# SchematicEasyEDA.net
KiCad netlist of a schematic drawn in EasyEDA
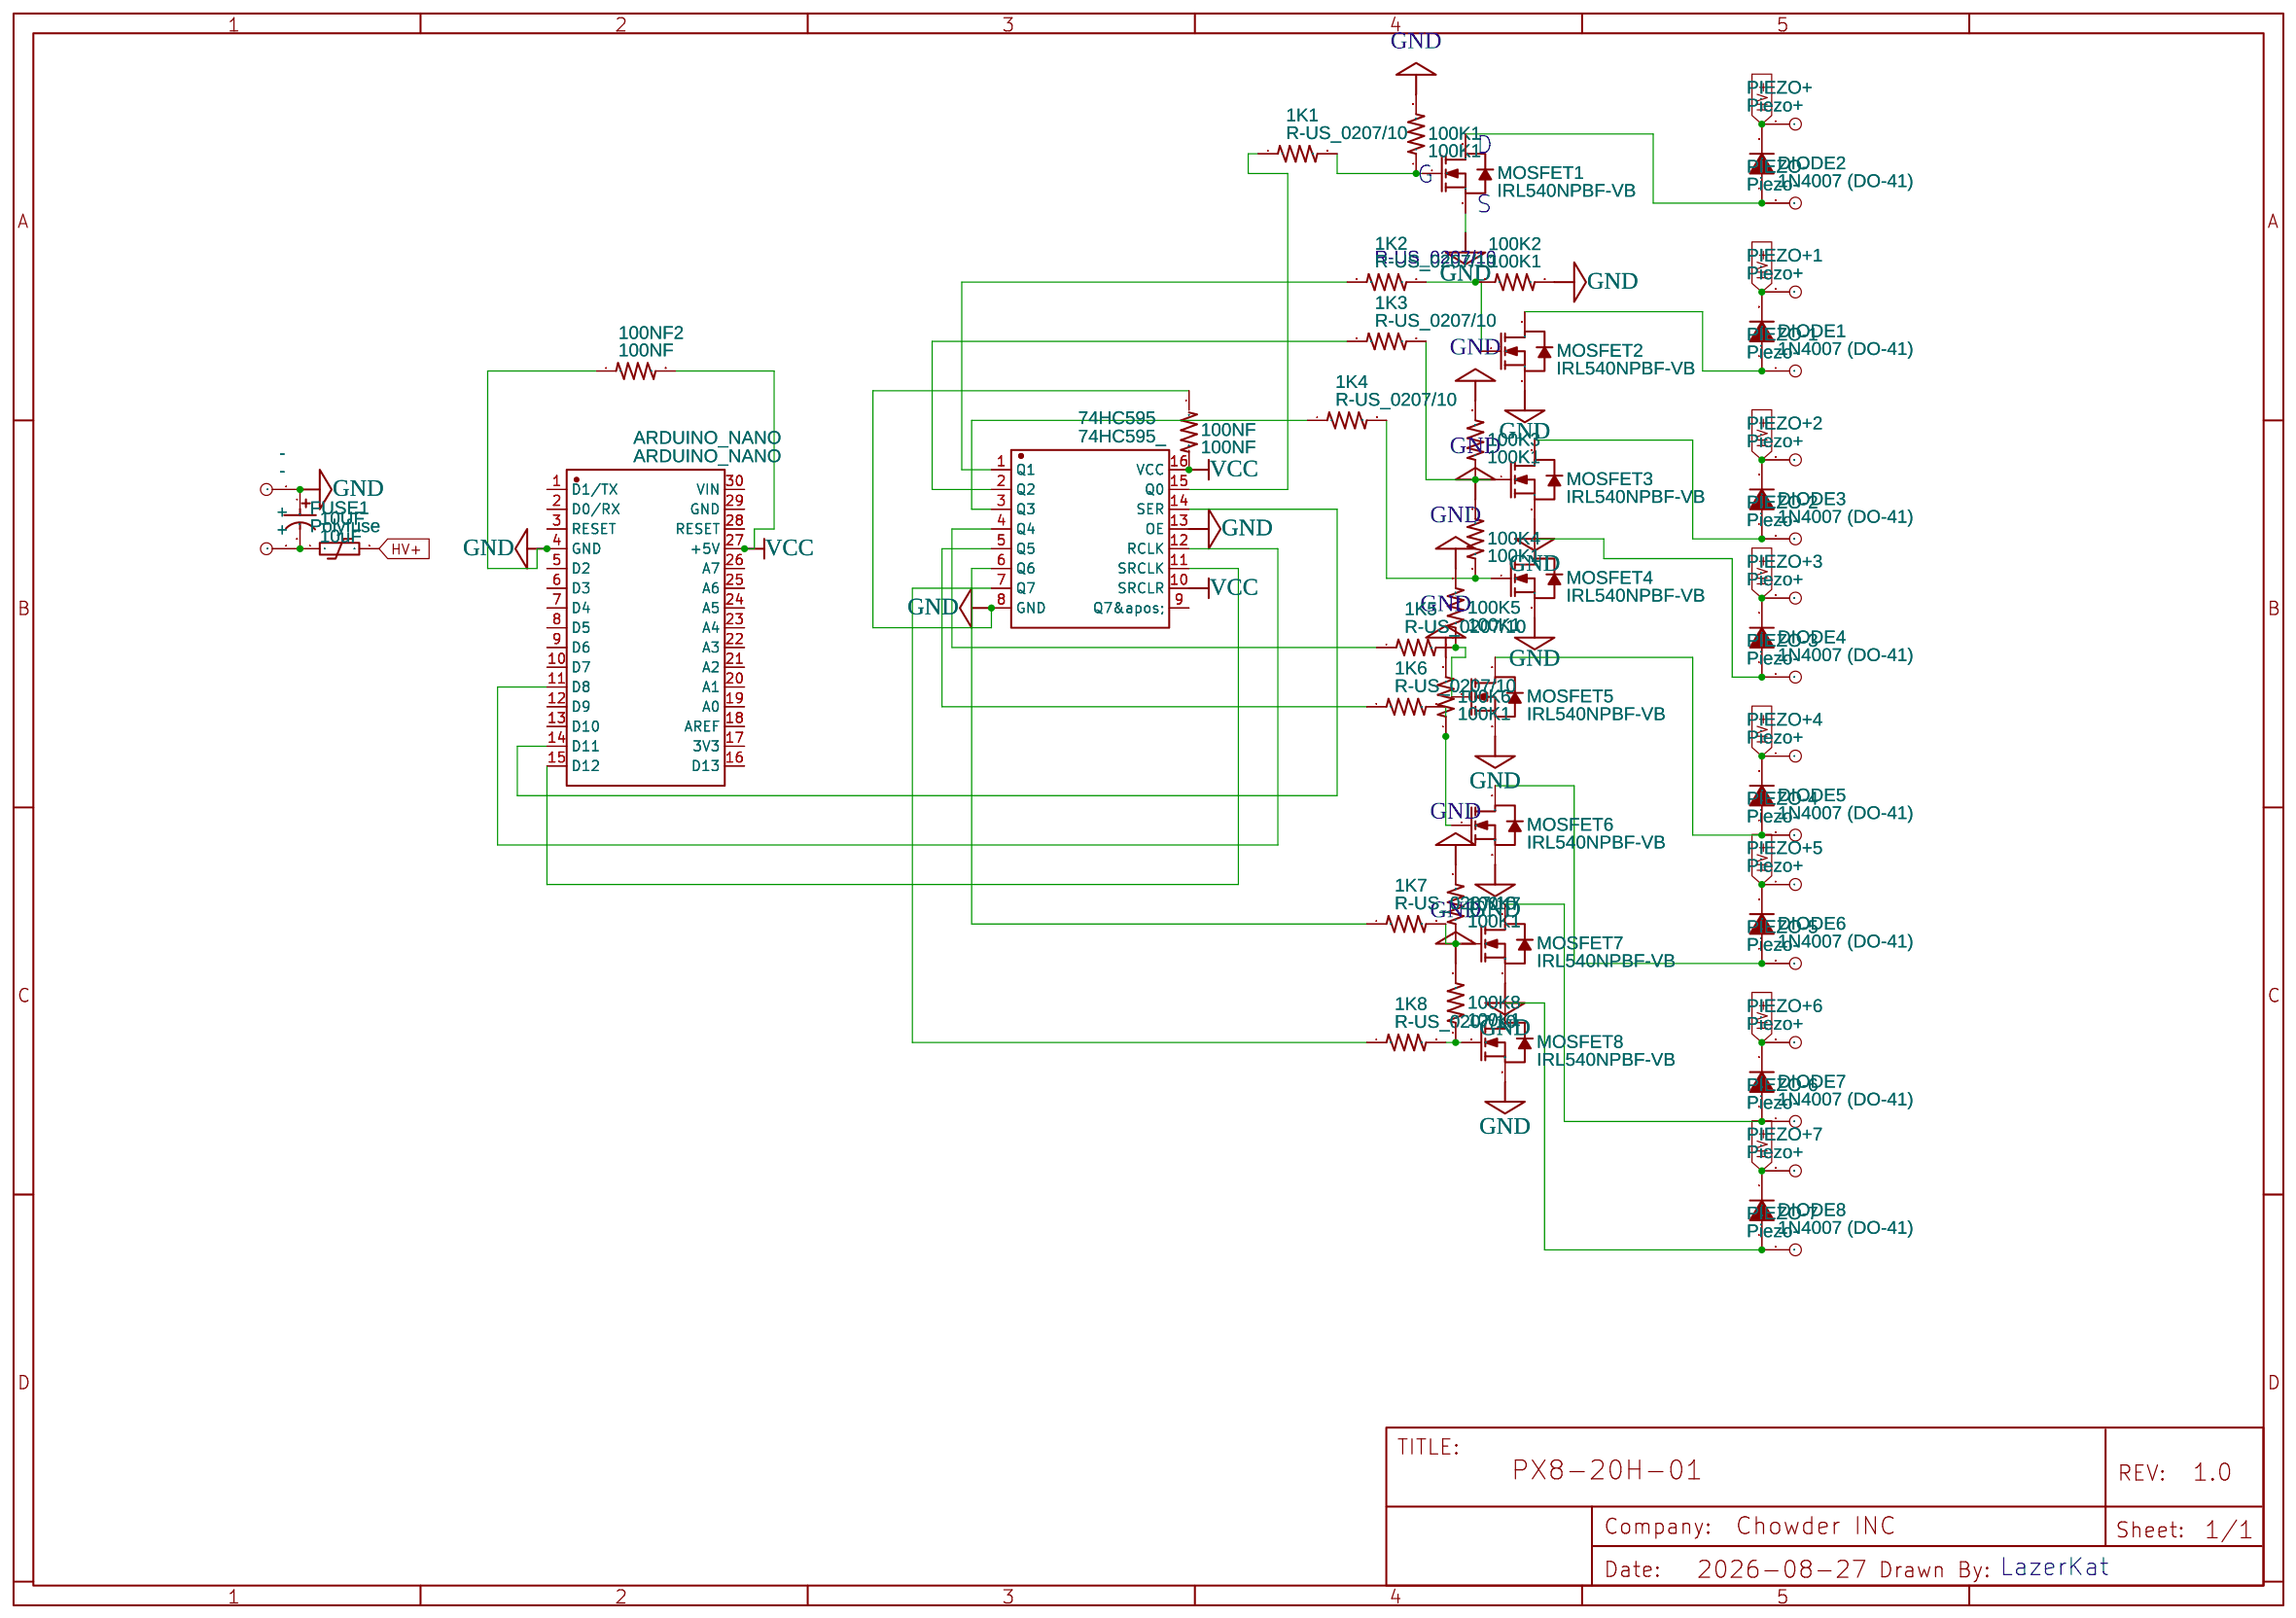
[diagram p0: schematic sheet]

(export (version "E")
  (design (tool "Eeschema 10.0.6"))
  (components
    (comp (ref "+") (value "+") (libsource (lib "") (part "Through-hole pin_3")))
    (comp (ref "-") (value "-") (libsource (lib "") (part "Through-hole pin_2")))
    (comp (ref "1K1") (value "R-US_0207/10") (libsource (lib "") (part "R-US_0207/10")))
    (comp (ref "1K2") (value "R-US_0207/10") (libsource (lib "") (part "R-US_0207/10")))
    (comp (ref "1K3") (value "R-US_0207/10") (libsource (lib "") (part "R-US_0207/10")))
    (comp (ref "1K4") (value "R-US_0207/10") (libsource (lib "") (part "R-US_0207/10")))
    (comp (ref "1K5") (value "R-US_0207/10") (libsource (lib "") (part "R-US_0207/10")))
    (comp (ref "1K6") (value "R-US_0207/10") (libsource (lib "") (part "R-US_0207/10")))
    (comp (ref "1K7") (value "R-US_0207/10") (libsource (lib "") (part "R-US_0207/10")))
    (comp (ref "1K8") (value "R-US_0207/10") (libsource (lib "") (part "R-US_0207/10")))
    (comp (ref "10UF")
      (value "10uF")
      (fields (field (name "Manufacturer Part") "ERS1KM100E11OT") (field (name "Manufacturer") "AISHI"))
      (libsource (lib "") (part "10UF 100V"))
    )
    (comp (ref "74HC595")
      (value "74HC595_")
      (fields (field (name "Manufacturer Part") "74HC595A") (field (name "Manufacturer") "FM"))
      (libsource (lib "") (part "74HC595_"))
    )
    (comp (ref "100K1") (value "100K1") (libsource (lib "") (part "R-US_0207/10_1")))
    (comp (ref "100K2") (value "100K1") (libsource (lib "") (part "R-US_0207/10_2")))
    (comp (ref "100K3") (value "100K1") (libsource (lib "") (part "R-US_0207/10_1")))
    (comp (ref "100K4") (value "100K1") (libsource (lib "") (part "R-US_0207/10_1")))
    (comp (ref "100K5") (value "100K1") (libsource (lib "") (part "R-US_0207/10_1")))
    (comp (ref "100K6") (value "100K1") (libsource (lib "") (part "R-US_0207/10_1")))
    (comp (ref "100K7") (value "100K1") (libsource (lib "") (part "R-US_0207/10_1")))
    (comp (ref "100K8") (value "100K1") (libsource (lib "") (part "R-US_0207/10_1")))
    (comp (ref "100NF") (value "100NF") (libsource (lib "") (part "R-US_0207/10_3")))
    (comp (ref "100NF2") (value "100NF") (libsource (lib "") (part "R-US_0207/10_4")))
    (comp (ref "ARDUINO_NANO") (value "ARDUINO_NANO") (libsource (lib "") (part "ARDUINO_NANO")))
    (comp (ref "DIODE1")
      (value "1N4007 (DO-41)")
      (fields (field (name "Manufacturer Part") "1 N 4007"))
      (libsource (lib "") (part "1N4007 (DO-41)"))
    )
    (comp (ref "DIODE2")
      (value "1N4007 (DO-41)")
      (fields (field (name "Manufacturer Part") "1 N 4007"))
      (libsource (lib "") (part "1N4007 (DO-41)"))
    )
    (comp (ref "DIODE3")
      (value "1N4007 (DO-41)")
      (fields (field (name "Manufacturer Part") "1 N 4007"))
      (libsource (lib "") (part "1N4007 (DO-41)"))
    )
    (comp (ref "DIODE4")
      (value "1N4007 (DO-41)")
      (fields (field (name "Manufacturer Part") "1 N 4007"))
      (libsource (lib "") (part "1N4007 (DO-41)"))
    )
    (comp (ref "DIODE5")
      (value "1N4007 (DO-41)")
      (fields (field (name "Manufacturer Part") "1 N 4007"))
      (libsource (lib "") (part "1N4007 (DO-41)"))
    )
    (comp (ref "DIODE6")
      (value "1N4007 (DO-41)")
      (fields (field (name "Manufacturer Part") "1 N 4007"))
      (libsource (lib "") (part "1N4007 (DO-41)"))
    )
    (comp (ref "DIODE7")
      (value "1N4007 (DO-41)")
      (fields (field (name "Manufacturer Part") "1 N 4007"))
      (libsource (lib "") (part "1N4007 (DO-41)"))
    )
    (comp (ref "DIODE8")
      (value "1N4007 (DO-41)")
      (fields (field (name "Manufacturer Part") "1 N 4007"))
      (libsource (lib "") (part "1N4007 (DO-41)"))
    )
    (comp (ref "FUSE1") (value "Polyfuse") (libsource (lib "") (part "Polyfuse")))
    (comp (ref "MOSFET1")
      (value "IRL540NPBF-VB")
      (fields (field (name "Manufacturer") "VBsemi(微碧半导体)"))
      (libsource (lib "") (part "IRL540NPBF-VB"))
    )
    (comp (ref "MOSFET2")
      (value "IRL540NPBF-VB")
      (fields (field (name "Manufacturer") "VBsemi(微碧半导体)"))
      (libsource (lib "") (part "IRL540NPBF-VB"))
    )
    (comp (ref "MOSFET3")
      (value "IRL540NPBF-VB")
      (fields (field (name "Manufacturer") "VBsemi(微碧半导体)"))
      (libsource (lib "") (part "IRL540NPBF-VB"))
    )
    (comp (ref "MOSFET4")
      (value "IRL540NPBF-VB")
      (fields (field (name "Manufacturer") "VBsemi(微碧半导体)"))
      (libsource (lib "") (part "IRL540NPBF-VB"))
    )
    (comp (ref "MOSFET5")
      (value "IRL540NPBF-VB")
      (fields (field (name "Manufacturer") "VBsemi(微碧半导体)"))
      (libsource (lib "") (part "IRL540NPBF-VB"))
    )
    (comp (ref "MOSFET6")
      (value "IRL540NPBF-VB")
      (fields (field (name "Manufacturer") "VBsemi(微碧半导体)"))
      (libsource (lib "") (part "IRL540NPBF-VB"))
    )
    (comp (ref "MOSFET7")
      (value "IRL540NPBF-VB")
      (fields (field (name "Manufacturer") "VBsemi(微碧半导体)"))
      (libsource (lib "") (part "IRL540NPBF-VB"))
    )
    (comp (ref "MOSFET8")
      (value "IRL540NPBF-VB")
      (fields (field (name "Manufacturer") "VBsemi(微碧半导体)"))
      (libsource (lib "") (part "IRL540NPBF-VB"))
    )
    (comp (ref "PIEZO+") (value "Piezo+") (libsource (lib "") (part "Through-hole pin_1")))
    (comp (ref "PIEZO+1") (value "Piezo+") (libsource (lib "") (part "Through-hole pin_1")))
    (comp (ref "PIEZO+2") (value "Piezo+") (libsource (lib "") (part "Through-hole pin_1")))
    (comp (ref "PIEZO+3") (value "Piezo+") (libsource (lib "") (part "Through-hole pin_1")))
    (comp (ref "PIEZO+4") (value "Piezo+") (libsource (lib "") (part "Through-hole pin_1")))
    (comp (ref "PIEZO+5") (value "Piezo+") (libsource (lib "") (part "Through-hole pin_1")))
    (comp (ref "PIEZO+6") (value "Piezo+") (libsource (lib "") (part "Through-hole pin_1")))
    (comp (ref "PIEZO+7") (value "Piezo+") (libsource (lib "") (part "Through-hole pin_1")))
    (comp (ref "PIEZO-") (value "Piezo-") (libsource (lib "") (part "Through-hole pin")))
    (comp (ref "PIEZO-1") (value "Piezo-") (libsource (lib "") (part "Through-hole pin")))
    (comp (ref "PIEZO-2") (value "Piezo-") (libsource (lib "") (part "Through-hole pin")))
    (comp (ref "PIEZO-3") (value "Piezo-") (libsource (lib "") (part "Through-hole pin")))
    (comp (ref "PIEZO-4") (value "Piezo-") (libsource (lib "") (part "Through-hole pin")))
    (comp (ref "PIEZO-5") (value "Piezo-") (libsource (lib "") (part "Through-hole pin")))
    (comp (ref "PIEZO-6") (value "Piezo-") (libsource (lib "") (part "Through-hole pin")))
    (comp (ref "PIEZO-7") (value "Piezo-") (libsource (lib "") (part "Through-hole pin")))
  )
  (nets
    (net (code "1") (name "GND") (class "Default")
      (node (ref "-") (pin "1") (pinfunction "1_1") (pintype "unspecified"))
      (node (ref "100K1") (pin "2") (pinfunction "2_2") (pintype "bidirectional"))
      (node (ref "100K2") (pin "2") (pinfunction "2_2") (pintype "bidirectional"))
      (node (ref "100K3") (pin "2") (pinfunction "2_2") (pintype "bidirectional"))
      (node (ref "100K4") (pin "2") (pinfunction "2_2") (pintype "bidirectional"))
      (node (ref "100K5") (pin "2") (pinfunction "2_2") (pintype "bidirectional"))
      (node (ref "100K6") (pin "2") (pinfunction "2_2") (pintype "bidirectional"))
      (node (ref "100K7") (pin "2") (pinfunction "2_2") (pintype "bidirectional"))
      (node (ref "100K8") (pin "2") (pinfunction "2_2") (pintype "bidirectional"))
      (node (ref "100NF") (pin "1") (pinfunction "1_1") (pintype "bidirectional"))
      (node (ref "100NF2") (pin "1") (pinfunction "1_1") (pintype "bidirectional"))
      (node (ref "10UF") (pin "1") (pinfunction "1_1") (pintype "input"))
      (node (ref "74HC595") (pin "13") (pinfunction "OE_13") (pintype "unspecified"))
      (node (ref "74HC595") (pin "8") (pinfunction "GND_8") (pintype "unspecified"))
      (node (ref "ARDUINO_NANO") (pin "4") (pinfunction "GND_4") (pintype "unspecified"))
      (node (ref "MOSFET1") (pin "3") (pinfunction "S_3") (pintype "unspecified"))
      (node (ref "MOSFET2") (pin "3") (pinfunction "S_3") (pintype "unspecified"))
      (node (ref "MOSFET3") (pin "3") (pinfunction "S_3") (pintype "unspecified"))
      (node (ref "MOSFET4") (pin "3") (pinfunction "S_3") (pintype "unspecified"))
      (node (ref "MOSFET5") (pin "3") (pinfunction "S_3") (pintype "unspecified"))
      (node (ref "MOSFET6") (pin "3") (pinfunction "S_3") (pintype "unspecified"))
      (node (ref "MOSFET7") (pin "3") (pinfunction "S_3") (pintype "unspecified"))
      (node (ref "MOSFET8") (pin "3") (pinfunction "S_3") (pintype "unspecified"))
    )
    (net (code "2") (name "HV+") (class "Default")
      (node (ref "DIODE1") (pin "C") (pinfunction "C_C") (pintype "unspecified"))
      (node (ref "DIODE2") (pin "C") (pinfunction "C_C") (pintype "unspecified"))
      (node (ref "DIODE3") (pin "C") (pinfunction "C_C") (pintype "unspecified"))
      (node (ref "DIODE4") (pin "C") (pinfunction "C_C") (pintype "unspecified"))
      (node (ref "DIODE5") (pin "C") (pinfunction "C_C") (pintype "unspecified"))
      (node (ref "DIODE6") (pin "C") (pinfunction "C_C") (pintype "unspecified"))
      (node (ref "DIODE7") (pin "C") (pinfunction "C_C") (pintype "unspecified"))
      (node (ref "DIODE8") (pin "C") (pinfunction "C_C") (pintype "unspecified"))
      (node (ref "FUSE1") (pin "2") (pinfunction "2_2") (pintype "unspecified"))
      (node (ref "PIEZO+") (pin "1") (pinfunction "1_1") (pintype "unspecified"))
      (node (ref "PIEZO+1") (pin "1") (pinfunction "1_1") (pintype "unspecified"))
      (node (ref "PIEZO+2") (pin "1") (pinfunction "1_1") (pintype "unspecified"))
      (node (ref "PIEZO+3") (pin "1") (pinfunction "1_1") (pintype "unspecified"))
      (node (ref "PIEZO+4") (pin "1") (pinfunction "1_1") (pintype "unspecified"))
      (node (ref "PIEZO+5") (pin "1") (pinfunction "1_1") (pintype "unspecified"))
      (node (ref "PIEZO+6") (pin "1") (pinfunction "1_1") (pintype "unspecified"))
      (node (ref "PIEZO+7") (pin "1") (pinfunction "1_1") (pintype "unspecified"))
    )
    (net (code "3") (name "Net-(+-Pad1)") (class "Default")
      (node (ref "+") (pin "1") (pinfunction "1_1") (pintype "unspecified"))
      (node (ref "10UF") (pin "2") (pinfunction "2_2") (pintype "input"))
      (node (ref "FUSE1") (pin "1") (pinfunction "1_1") (pintype "unspecified"))
    )
    (net (code "4") (name "Net-(74HC595-Q0)") (class "Default")
      (node (ref "1K1") (pin "1") (pinfunction "1_1") (pintype "bidirectional"))
      (node (ref "74HC595") (pin "15") (pinfunction "Q0_15") (pintype "unspecified"))
    )
    (net (code "5") (name "Net-(74HC595-Q1)") (class "Default")
      (node (ref "1K2") (pin "1") (pinfunction "1_1") (pintype "bidirectional"))
      (node (ref "74HC595") (pin "1") (pinfunction "Q1_1") (pintype "unspecified"))
    )
    (net (code "6") (name "Net-(74HC595-Q2)") (class "Default")
      (node (ref "1K3") (pin "1") (pinfunction "1_1") (pintype "bidirectional"))
      (node (ref "74HC595") (pin "2") (pinfunction "Q2_2") (pintype "unspecified"))
    )
    (net (code "7") (name "Net-(74HC595-Q3)") (class "Default")
      (node (ref "1K4") (pin "1") (pinfunction "1_1") (pintype "bidirectional"))
      (node (ref "74HC595") (pin "3") (pinfunction "Q3_3") (pintype "unspecified"))
    )
    (net (code "8") (name "Net-(74HC595-Q4)") (class "Default")
      (node (ref "1K5") (pin "1") (pinfunction "1_1") (pintype "bidirectional"))
      (node (ref "74HC595") (pin "4") (pinfunction "Q4_4") (pintype "unspecified"))
    )
    (net (code "9") (name "Net-(74HC595-Q5)") (class "Default")
      (node (ref "1K6") (pin "1") (pinfunction "1_1") (pintype "bidirectional"))
      (node (ref "74HC595") (pin "5") (pinfunction "Q5_5") (pintype "unspecified"))
    )
    (net (code "10") (name "Net-(74HC595-Q6)") (class "Default")
      (node (ref "1K7") (pin "1") (pinfunction "1_1") (pintype "bidirectional"))
      (node (ref "74HC595") (pin "6") (pinfunction "Q6_6") (pintype "unspecified"))
    )
    (net (code "11") (name "Net-(74HC595-Q7)") (class "Default")
      (node (ref "1K8") (pin "1") (pinfunction "1_1") (pintype "bidirectional"))
      (node (ref "74HC595") (pin "7") (pinfunction "Q7_7") (pintype "unspecified"))
    )
    (net (code "12") (name "Net-(74HC595-RCLK)") (class "Default")
      (node (ref "74HC595") (pin "12") (pinfunction "RCLK_12") (pintype "unspecified"))
      (node (ref "ARDUINO_NANO") (pin "11") (pinfunction "D8_11") (pintype "unspecified"))
    )
    (net (code "13") (name "Net-(74HC595-SER)") (class "Default")
      (node (ref "74HC595") (pin "14") (pinfunction "SER_14") (pintype "unspecified"))
      (node (ref "ARDUINO_NANO") (pin "14") (pinfunction "D11_14") (pintype "unspecified"))
    )
    (net (code "14") (name "Net-(74HC595-SRCLK)") (class "Default")
      (node (ref "74HC595") (pin "11") (pinfunction "SRCLK_11") (pintype "unspecified"))
      (node (ref "ARDUINO_NANO") (pin "15") (pinfunction "D12_15") (pintype "unspecified"))
    )
    (net (code "15") (name "Net-(MOSFET1-D)") (class "Default")
      (node (ref "DIODE2") (pin "A") (pinfunction "A_A") (pintype "unspecified"))
      (node (ref "MOSFET1") (pin "2") (pinfunction "D_2") (pintype "unspecified"))
      (node (ref "PIEZO-") (pin "1") (pinfunction "1_1") (pintype "unspecified"))
    )
    (net (code "16") (name "Net-(MOSFET1-G)") (class "Default")
      (node (ref "100K1") (pin "1") (pinfunction "1_1") (pintype "bidirectional"))
      (node (ref "1K1") (pin "2") (pinfunction "2_2") (pintype "bidirectional"))
      (node (ref "MOSFET1") (pin "1") (pinfunction "G_1") (pintype "unspecified"))
    )
    (net (code "17") (name "Net-(MOSFET2-D)") (class "Default")
      (node (ref "DIODE1") (pin "A") (pinfunction "A_A") (pintype "unspecified"))
      (node (ref "MOSFET2") (pin "2") (pinfunction "D_2") (pintype "unspecified"))
      (node (ref "PIEZO-1") (pin "1") (pinfunction "1_1") (pintype "unspecified"))
    )
    (net (code "18") (name "Net-(MOSFET2-G)") (class "Default")
      (node (ref "100K2") (pin "1") (pinfunction "1_1") (pintype "bidirectional"))
      (node (ref "1K2") (pin "2") (pinfunction "2_2") (pintype "bidirectional"))
      (node (ref "MOSFET2") (pin "1") (pinfunction "G_1") (pintype "unspecified"))
    )
    (net (code "19") (name "Net-(MOSFET3-D)") (class "Default")
      (node (ref "DIODE3") (pin "A") (pinfunction "A_A") (pintype "unspecified"))
      (node (ref "MOSFET3") (pin "2") (pinfunction "D_2") (pintype "unspecified"))
      (node (ref "PIEZO-2") (pin "1") (pinfunction "1_1") (pintype "unspecified"))
    )
    (net (code "20") (name "Net-(MOSFET3-G)") (class "Default")
      (node (ref "100K3") (pin "1") (pinfunction "1_1") (pintype "bidirectional"))
      (node (ref "1K3") (pin "2") (pinfunction "2_2") (pintype "bidirectional"))
      (node (ref "MOSFET3") (pin "1") (pinfunction "G_1") (pintype "unspecified"))
    )
    (net (code "21") (name "Net-(MOSFET4-D)") (class "Default")
      (node (ref "DIODE4") (pin "A") (pinfunction "A_A") (pintype "unspecified"))
      (node (ref "MOSFET4") (pin "2") (pinfunction "D_2") (pintype "unspecified"))
      (node (ref "PIEZO-3") (pin "1") (pinfunction "1_1") (pintype "unspecified"))
    )
    (net (code "22") (name "Net-(MOSFET4-G)") (class "Default")
      (node (ref "100K4") (pin "1") (pinfunction "1_1") (pintype "bidirectional"))
      (node (ref "1K4") (pin "2") (pinfunction "2_2") (pintype "bidirectional"))
      (node (ref "MOSFET4") (pin "1") (pinfunction "G_1") (pintype "unspecified"))
    )
    (net (code "23") (name "Net-(MOSFET5-D)") (class "Default")
      (node (ref "DIODE5") (pin "A") (pinfunction "A_A") (pintype "unspecified"))
      (node (ref "MOSFET5") (pin "2") (pinfunction "D_2") (pintype "unspecified"))
      (node (ref "PIEZO-4") (pin "1") (pinfunction "1_1") (pintype "unspecified"))
    )
    (net (code "24") (name "Net-(MOSFET5-G)") (class "Default")
      (node (ref "100K5") (pin "1") (pinfunction "1_1") (pintype "bidirectional"))
      (node (ref "1K5") (pin "2") (pinfunction "2_2") (pintype "bidirectional"))
      (node (ref "MOSFET5") (pin "1") (pinfunction "G_1") (pintype "unspecified"))
    )
    (net (code "25") (name "Net-(MOSFET6-D)") (class "Default")
      (node (ref "DIODE6") (pin "A") (pinfunction "A_A") (pintype "unspecified"))
      (node (ref "MOSFET6") (pin "2") (pinfunction "D_2") (pintype "unspecified"))
      (node (ref "PIEZO-5") (pin "1") (pinfunction "1_1") (pintype "unspecified"))
    )
    (net (code "26") (name "Net-(MOSFET6-G)") (class "Default")
      (node (ref "100K6") (pin "1") (pinfunction "1_1") (pintype "bidirectional"))
      (node (ref "1K6") (pin "2") (pinfunction "2_2") (pintype "bidirectional"))
      (node (ref "MOSFET6") (pin "1") (pinfunction "G_1") (pintype "unspecified"))
    )
    (net (code "27") (name "Net-(MOSFET7-D)") (class "Default")
      (node (ref "DIODE7") (pin "A") (pinfunction "A_A") (pintype "unspecified"))
      (node (ref "MOSFET7") (pin "2") (pinfunction "D_2") (pintype "unspecified"))
      (node (ref "PIEZO-6") (pin "1") (pinfunction "1_1") (pintype "unspecified"))
    )
    (net (code "28") (name "Net-(MOSFET7-G)") (class "Default")
      (node (ref "100K7") (pin "1") (pinfunction "1_1") (pintype "bidirectional"))
      (node (ref "1K7") (pin "2") (pinfunction "2_2") (pintype "bidirectional"))
      (node (ref "MOSFET7") (pin "1") (pinfunction "G_1") (pintype "unspecified"))
    )
    (net (code "29") (name "Net-(MOSFET8-D)") (class "Default")
      (node (ref "DIODE8") (pin "A") (pinfunction "A_A") (pintype "unspecified"))
      (node (ref "MOSFET8") (pin "2") (pinfunction "D_2") (pintype "unspecified"))
      (node (ref "PIEZO-7") (pin "1") (pinfunction "1_1") (pintype "unspecified"))
    )
    (net (code "30") (name "Net-(MOSFET8-G)") (class "Default")
      (node (ref "100K8") (pin "1") (pinfunction "1_1") (pintype "bidirectional"))
      (node (ref "1K8") (pin "2") (pinfunction "2_2") (pintype "bidirectional"))
      (node (ref "MOSFET8") (pin "1") (pinfunction "G_1") (pintype "unspecified"))
    )
    (net (code "31") (name "VCC") (class "Default")
      (node (ref "100NF") (pin "2") (pinfunction "2_2") (pintype "bidirectional"))
      (node (ref "100NF2") (pin "2") (pinfunction "2_2") (pintype "bidirectional"))
      (node (ref "74HC595") (pin "10") (pinfunction "SRCLR_10") (pintype "unspecified"))
      (node (ref "74HC595") (pin "16") (pinfunction "VCC_16") (pintype "unspecified"))
      (node (ref "ARDUINO_NANO") (pin "27") (pinfunction "+5V_27") (pintype "unspecified"))
    )
    (net (code "32") (name "unconnected-(74HC595-Q7&apos;-Pad9)") (class "Default")
      (node (ref "74HC595") (pin "9") (pinfunction "Q7&apos;_9") (pintype "unspecified"))
    )
    (net (code "33") (name "unconnected-(ARDUINO_NANO-3V3-Pad17)") (class "Default")
      (node (ref "ARDUINO_NANO") (pin "17") (pinfunction "3V3_17") (pintype "unspecified"))
    )
    (net (code "34") (name "unconnected-(ARDUINO_NANO-A0-Pad19)") (class "Default")
      (node (ref "ARDUINO_NANO") (pin "19") (pinfunction "A0_19") (pintype "unspecified"))
    )
    (net (code "35") (name "unconnected-(ARDUINO_NANO-A1-Pad20)") (class "Default")
      (node (ref "ARDUINO_NANO") (pin "20") (pinfunction "A1_20") (pintype "unspecified"))
    )
    (net (code "36") (name "unconnected-(ARDUINO_NANO-A2-Pad21)") (class "Default")
      (node (ref "ARDUINO_NANO") (pin "21") (pinfunction "A2_21") (pintype "unspecified"))
    )
    (net (code "37") (name "unconnected-(ARDUINO_NANO-A3-Pad22)") (class "Default")
      (node (ref "ARDUINO_NANO") (pin "22") (pinfunction "A3_22") (pintype "unspecified"))
    )
    (net (code "38") (name "unconnected-(ARDUINO_NANO-A4-Pad23)") (class "Default")
      (node (ref "ARDUINO_NANO") (pin "23") (pinfunction "A4_23") (pintype "unspecified"))
    )
    (net (code "39") (name "unconnected-(ARDUINO_NANO-A5-Pad24)") (class "Default")
      (node (ref "ARDUINO_NANO") (pin "24") (pinfunction "A5_24") (pintype "unspecified"))
    )
    (net (code "40") (name "unconnected-(ARDUINO_NANO-A6-Pad25)") (class "Default")
      (node (ref "ARDUINO_NANO") (pin "25") (pinfunction "A6_25") (pintype "unspecified"))
    )
    (net (code "41") (name "unconnected-(ARDUINO_NANO-A7-Pad26)") (class "Default")
      (node (ref "ARDUINO_NANO") (pin "26") (pinfunction "A7_26") (pintype "unspecified"))
    )
    (net (code "42") (name "unconnected-(ARDUINO_NANO-AREF-Pad18)") (class "Default")
      (node (ref "ARDUINO_NANO") (pin "18") (pinfunction "AREF_18") (pintype "unspecified"))
    )
    (net (code "43") (name "unconnected-(ARDUINO_NANO-D0{slash}RX-Pad2)") (class "Default")
      (node (ref "ARDUINO_NANO") (pin "2") (pinfunction "D0/RX_2") (pintype "unspecified"))
    )
    (net (code "44") (name "unconnected-(ARDUINO_NANO-D1{slash}TX-Pad1)") (class "Default")
      (node (ref "ARDUINO_NANO") (pin "1") (pinfunction "D1/TX_1") (pintype "unspecified"))
    )
    (net (code "45") (name "unconnected-(ARDUINO_NANO-D2-Pad5)") (class "Default")
      (node (ref "ARDUINO_NANO") (pin "5") (pinfunction "D2_5") (pintype "unspecified"))
    )
    (net (code "46") (name "unconnected-(ARDUINO_NANO-D3-Pad6)") (class "Default")
      (node (ref "ARDUINO_NANO") (pin "6") (pinfunction "D3_6") (pintype "unspecified"))
    )
    (net (code "47") (name "unconnected-(ARDUINO_NANO-D4-Pad7)") (class "Default")
      (node (ref "ARDUINO_NANO") (pin "7") (pinfunction "D4_7") (pintype "unspecified"))
    )
    (net (code "48") (name "unconnected-(ARDUINO_NANO-D5-Pad8)") (class "Default")
      (node (ref "ARDUINO_NANO") (pin "8") (pinfunction "D5_8") (pintype "unspecified"))
    )
    (net (code "49") (name "unconnected-(ARDUINO_NANO-D6-Pad9)") (class "Default")
      (node (ref "ARDUINO_NANO") (pin "9") (pinfunction "D6_9") (pintype "unspecified"))
    )
    (net (code "50") (name "unconnected-(ARDUINO_NANO-D7-Pad10)") (class "Default")
      (node (ref "ARDUINO_NANO") (pin "10") (pinfunction "D7_10") (pintype "unspecified"))
    )
    (net (code "51") (name "unconnected-(ARDUINO_NANO-D9-Pad12)") (class "Default")
      (node (ref "ARDUINO_NANO") (pin "12") (pinfunction "D9_12") (pintype "unspecified"))
    )
    (net (code "52") (name "unconnected-(ARDUINO_NANO-D10-Pad13)") (class "Default")
      (node (ref "ARDUINO_NANO") (pin "13") (pinfunction "D10_13") (pintype "unspecified"))
    )
    (net (code "53") (name "unconnected-(ARDUINO_NANO-D13-Pad16)") (class "Default")
      (node (ref "ARDUINO_NANO") (pin "16") (pinfunction "D13_16") (pintype "unspecified"))
    )
    (net (code "54") (name "unconnected-(ARDUINO_NANO-GND-Pad29)") (class "Default")
      (node (ref "ARDUINO_NANO") (pin "29") (pinfunction "GND_29") (pintype "unspecified"))
    )
    (net (code "55") (name "unconnected-(ARDUINO_NANO-RESET-Pad3)") (class "Default")
      (node (ref "ARDUINO_NANO") (pin "3") (pinfunction "RESET_3") (pintype "unspecified"))
    )
    (net (code "56") (name "unconnected-(ARDUINO_NANO-RESET-Pad28)") (class "Default")
      (node (ref "ARDUINO_NANO") (pin "28") (pinfunction "RESET_28") (pintype "unspecified"))
    )
    (net (code "57") (name "unconnected-(ARDUINO_NANO-VIN-Pad30)") (class "Default")
      (node (ref "ARDUINO_NANO") (pin "30") (pinfunction "VIN_30") (pintype "unspecified"))
    )
  )
)
